# 2020210905-jiajunliANALOG.net
KiCad netlist of a schematic drawn in Altium Designer
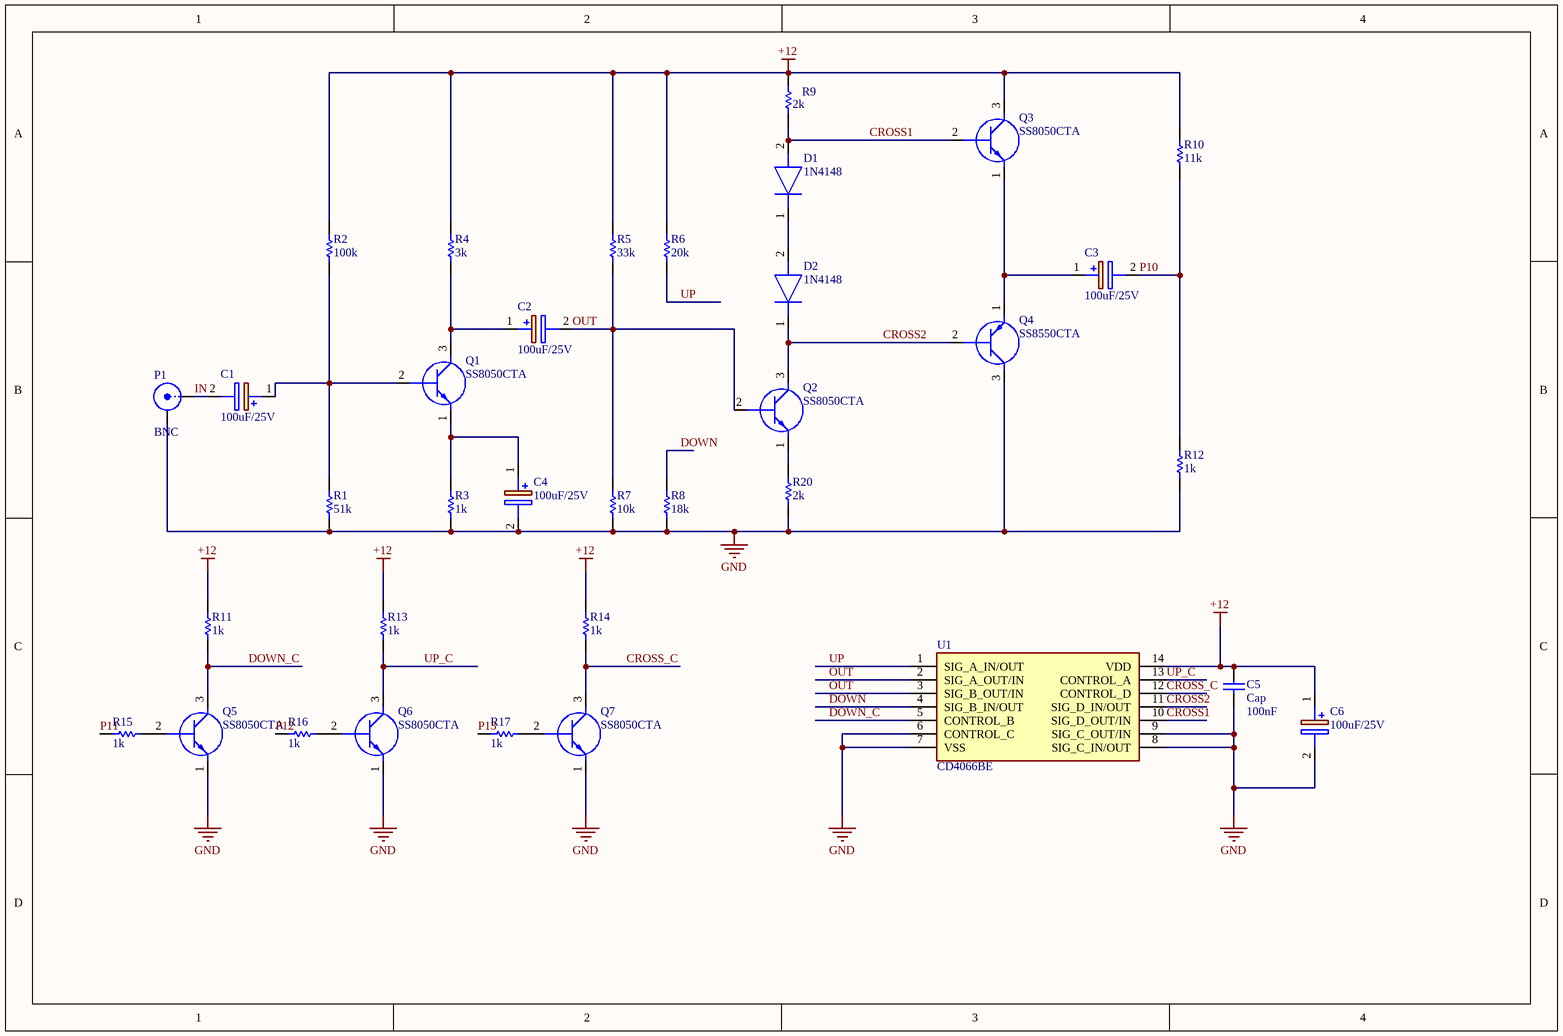
[diagram p0: 2020210905-jiajunliANALOG.SchDoc]

(export (version "E")
  (design (tool "Eeschema 10.0.6"))
  (components
    (comp (ref "C1")
      (value "100uF/25V")
      (footprint "CAPPRD350W65D800H1250")
      (description "Capacitor Polarised")
      (fields
        (field (name "MANUFACTURER_PART_NUMBER") "ECA-1EEN101")
        (field (name "MOUSER PART NUMBER") "667-ECA-1EEN101")
      )
      (libsource (lib "") (part "ECA-1EEN101_1"))
    )
    (comp (ref "C2")
      (value "100uF/25V")
      (footprint "CAPPRD350W65D800H1250")
      (description "Capacitor Polarised")
      (fields
        (field (name "MANUFACTURER_PART_NUMBER") "ECA-1EEN101")
        (field (name "MOUSER PART NUMBER") "667-ECA-1EEN101")
      )
      (libsource (lib "THD-LIB") (part "ECA-1EEN101"))
    )
    (comp (ref "C3")
      (value "100uF/25V")
      (footprint "CAPPRD350W65D800H1250")
      (description "Capacitor Polarised")
      (fields
        (field (name "MANUFACTURER_PART_NUMBER") "ECA-1EEN101")
        (field (name "MOUSER PART NUMBER") "667-ECA-1EEN101")
      )
      (libsource (lib "THD-LIB") (part "ECA-1EEN101"))
    )
    (comp (ref "C4")
      (value "100uF/25V")
      (footprint "CAPPRD350W65D800H1250")
      (description "Capacitor Polarised")
      (fields
        (field (name "MANUFACTURER_PART_NUMBER") "ECA-1EEN101")
        (field (name "MOUSER PART NUMBER") "667-ECA-1EEN101")
      )
      (libsource (lib "") (part "ECA-1EEN101_2"))
    )
    (comp (ref "C5")
      (value "Cap")
      (footprint "RAD-0.2-cap")
      (description "Capacitor")
      (fields (field (name "ALTIUM_VALUE") "100nF") (field (name "PUBLISHER") "Altium Limited"))
      (libsource (lib "THD-LIB") (part "Cap"))
    )
    (comp (ref "C6")
      (value "100uF/25V")
      (footprint "CAPPRD350W65D800H1250")
      (description "Capacitor Polarised")
      (fields
        (field (name "MANUFACTURER_PART_NUMBER") "ECA-1EEN101")
        (field (name "MOUSER PART NUMBER") "667-ECA-1EEN101")
      )
      (libsource (lib "") (part "ECA-1EEN101_2"))
    )
    (comp (ref "D1")
      (value "1N4148")
      (footprint "DIOAD1068W53L380D172")
      (description "Diode")
      (fields (field (name "MOUSER PART NUMBER") "512-1N4148"))
      (libsource (lib "THD-LIB") (part "1N4148"))
    )
    (comp (ref "D2")
      (value "1N4148")
      (footprint "DIOAD1068W53L380D172")
      (description "Diode")
      (fields (field (name "MOUSER PART NUMBER") "512-1N4148"))
      (libsource (lib "THD-LIB") (part "1N4148"))
    )
    (comp (ref "P1")
      (value "BNC")
      (footprint "BNC_RA-CON")
      (description "BNC Elbow Connector")
      (fields (field (name "PUBLISHER") "Altium Limited"))
      (libsource (lib "THD-LIB") (part "BNC"))
    )
    (comp (ref "Q1")
      (value "SS8050CTA")
      (footprint "TO-92-3")
      (description "Transistor BJT NPN")
      (fields (field (name "MOUSER PART NUMBER") "512-SS8050CTA"))
      (libsource (lib "THD-LIB") (part "SS8050CTA"))
    )
    (comp (ref "Q2")
      (value "SS8050CTA")
      (footprint "TO-92-3")
      (description "Transistor BJT NPN")
      (fields (field (name "MOUSER PART NUMBER") "512-SS8050CTA"))
      (libsource (lib "THD-LIB") (part "SS8050CTA"))
    )
    (comp (ref "Q3")
      (value "SS8050CTA")
      (footprint "TO-92-3")
      (description "Transistor BJT NPN")
      (fields (field (name "MOUSER PART NUMBER") "512-SS8050CTA"))
      (libsource (lib "THD-LIB") (part "SS8050CTA"))
    )
    (comp (ref "Q4")
      (value "SS8550CTA")
      (footprint "TO-92-3")
      (description "Transistor BJT PNP")
      (fields (field (name "MOUSER PART NUMBER") "512-SS8550CTA"))
      (libsource (lib "THD-LIB") (part "SS8550CTA"))
    )
    (comp (ref "Q5")
      (value "SS8050CTA")
      (footprint "TO-92-3")
      (description "Transistor BJT NPN")
      (fields (field (name "MOUSER PART NUMBER") "512-SS8050CTA"))
      (libsource (lib "THD-LIB") (part "SS8050CTA"))
    )
    (comp (ref "Q6")
      (value "SS8050CTA")
      (footprint "TO-92-3")
      (description "Transistor BJT NPN")
      (fields (field (name "MOUSER PART NUMBER") "512-SS8050CTA"))
      (libsource (lib "THD-LIB") (part "SS8050CTA"))
    )
    (comp (ref "Q7")
      (value "SS8050CTA")
      (footprint "TO-92-3")
      (description "Transistor BJT NPN")
      (fields (field (name "MOUSER PART NUMBER") "512-SS8050CTA"))
      (libsource (lib "THD-LIB") (part "SS8050CTA"))
    )
    (comp (ref "R1")
      (value "51k")
      (footprint "RES-AXIAL-0.4")
      (description "Resistor")
      (fields (field (name "PUBLISHER") "Altium Limited"))
      (libsource (lib "THD-LIB") (part "Res1"))
    )
    (comp (ref "R2")
      (value "100k")
      (footprint "RES-AXIAL-0.4")
      (description "Resistor")
      (fields (field (name "PUBLISHER") "Altium Limited"))
      (libsource (lib "THD-LIB") (part "Res1"))
    )
    (comp (ref "R3")
      (value "1k")
      (footprint "RES-AXIAL-0.4")
      (description "Resistor")
      (fields (field (name "PUBLISHER") "Altium Limited"))
      (libsource (lib "THD-LIB") (part "Res1"))
    )
    (comp (ref "R4")
      (value "3k")
      (footprint "RES-AXIAL-0.4")
      (description "Resistor")
      (fields (field (name "PUBLISHER") "Altium Limited"))
      (libsource (lib "THD-LIB") (part "Res1"))
    )
    (comp (ref "R5")
      (value "33k")
      (footprint "RES-AXIAL-0.4")
      (description "Resistor")
      (fields (field (name "PUBLISHER") "Altium Limited"))
      (libsource (lib "THD-LIB") (part "Res1"))
    )
    (comp (ref "R6")
      (value "20k")
      (footprint "RES-AXIAL-0.4")
      (description "Resistor")
      (fields (field (name "PUBLISHER") "Altium Limited"))
      (libsource (lib "THD-LIB") (part "Res1"))
    )
    (comp (ref "R7")
      (value "10k")
      (footprint "RES-AXIAL-0.4")
      (description "Resistor")
      (fields (field (name "PUBLISHER") "Altium Limited"))
      (libsource (lib "THD-LIB") (part "Res1"))
    )
    (comp (ref "R8")
      (value "18k")
      (footprint "RES-AXIAL-0.4")
      (description "Resistor")
      (fields (field (name "PUBLISHER") "Altium Limited"))
      (libsource (lib "THD-LIB") (part "Res1"))
    )
    (comp (ref "R9")
      (value "2k")
      (footprint "RES-AXIAL-0.4")
      (description "Resistor")
      (fields (field (name "PUBLISHER") "Altium Limited"))
      (libsource (lib "THD-LIB") (part "Res1"))
    )
    (comp (ref "R10")
      (value "11k")
      (footprint "RES-AXIAL-0.4")
      (description "Resistor")
      (fields (field (name "PUBLISHER") "Altium Limited"))
      (libsource (lib "THD-LIB") (part "Res1"))
    )
    (comp (ref "R11")
      (value "1k")
      (footprint "RES-AXIAL-0.4")
      (description "Resistor")
      (fields (field (name "PUBLISHER") "Altium Limited"))
      (libsource (lib "THD-LIB") (part "Res1"))
    )
    (comp (ref "R12")
      (value "1k")
      (footprint "RES-AXIAL-0.4")
      (description "Resistor")
      (fields (field (name "PUBLISHER") "Altium Limited"))
      (libsource (lib "THD-LIB") (part "Res1"))
    )
    (comp (ref "R13")
      (value "1k")
      (footprint "RES-AXIAL-0.4")
      (description "Resistor")
      (fields (field (name "PUBLISHER") "Altium Limited"))
      (libsource (lib "THD-LIB") (part "Res1"))
    )
    (comp (ref "R14")
      (value "1k")
      (footprint "RES-AXIAL-0.4")
      (description "Resistor")
      (fields (field (name "PUBLISHER") "Altium Limited"))
      (libsource (lib "THD-LIB") (part "Res1"))
    )
    (comp (ref "R15")
      (value "1k")
      (footprint "RES-AXIAL-0.4")
      (description "Resistor")
      (fields (field (name "PUBLISHER") "Altium Limited"))
      (libsource (lib "THD-LIB") (part "Res1"))
    )
    (comp (ref "R16")
      (value "1k")
      (footprint "RES-AXIAL-0.4")
      (description "Resistor")
      (fields (field (name "PUBLISHER") "Altium Limited"))
      (libsource (lib "THD-LIB") (part "Res1"))
    )
    (comp (ref "R17")
      (value "1k")
      (footprint "RES-AXIAL-0.4")
      (description "Resistor")
      (fields (field (name "PUBLISHER") "Altium Limited"))
      (libsource (lib "THD-LIB") (part "Res1"))
    )
    (comp (ref "R20")
      (value "2k")
      (footprint "RES-AXIAL-0.4")
      (description "Resistor")
      (fields (field (name "PUBLISHER") "Altium Limited"))
      (libsource (lib "THD-LIB") (part "Res1"))
    )
    (comp (ref "U1")
      (value "CD4066BE")
      (footprint "DIP794W53P254L1930H508Q14N")
      (description "Integrated Circuit")
      (fields (field (name "MOUSER PART NUMBER") "595-CD4066BE"))
      (libsource (lib "THD-LIB") (part "CD4066BE"))
    )
  )
  (nets
    (net (code "1") (name "+12") (class "Default")
      (node (ref "C5") (pin "2") (pinfunction "2_2") (pintype "passive"))
      (node (ref "C6") (pin "1") (pinfunction "+_1") (pintype "passive"))
      (node (ref "Q3") (pin "3") (pinfunction "C_3") (pintype "passive"))
      (node (ref "R10") (pin "2") (pinfunction "2_2") (pintype "passive"))
      (node (ref "R11") (pin "2") (pinfunction "2_2") (pintype "passive"))
      (node (ref "R13") (pin "2") (pinfunction "2_2") (pintype "passive"))
      (node (ref "R14") (pin "2") (pinfunction "2_2") (pintype "passive"))
      (node (ref "R2") (pin "2") (pinfunction "2_2") (pintype "passive"))
      (node (ref "R4") (pin "2") (pinfunction "2_2") (pintype "passive"))
      (node (ref "R5") (pin "2") (pinfunction "2_2") (pintype "passive"))
      (node (ref "R6") (pin "2") (pinfunction "2_2") (pintype "passive"))
      (node (ref "R9") (pin "2") (pinfunction "2_2") (pintype "passive"))
      (node (ref "U1") (pin "14") (pinfunction "VDD_14") (pintype "passive"))
    )
    (net (code "2") (name "/CROSS1") (class "Default")
      (node (ref "D1") (pin "2") (pinfunction "A_2") (pintype "passive"))
      (node (ref "Q3") (pin "2") (pinfunction "B_2") (pintype "passive"))
      (node (ref "R9") (pin "1") (pinfunction "1_1") (pintype "passive"))
      (node (ref "U1") (pin "10") (pinfunction "SIG_D_OUT/IN_10") (pintype "passive"))
    )
    (net (code "3") (name "/CROSS2") (class "Default")
      (node (ref "D2") (pin "1") (pinfunction "K_1") (pintype "passive"))
      (node (ref "Q2") (pin "3") (pinfunction "C_3") (pintype "passive"))
      (node (ref "Q4") (pin "2") (pinfunction "B_2") (pintype "passive"))
      (node (ref "U1") (pin "11") (pinfunction "SIG_D_IN/OUT_11") (pintype "passive"))
    )
    (net (code "4") (name "/CROSS_C") (class "Default")
      (node (ref "Q7") (pin "3") (pinfunction "C_3") (pintype "passive"))
      (node (ref "R14") (pin "1") (pinfunction "1_1") (pintype "passive"))
      (node (ref "U1") (pin "12") (pinfunction "CONTROL_D_12") (pintype "passive"))
    )
    (net (code "5") (name "/DOWN") (class "Default")
      (node (ref "R8") (pin "2") (pinfunction "2_2") (pintype "passive"))
      (node (ref "U1") (pin "4") (pinfunction "SIG_B_IN/OUT_4") (pintype "passive"))
    )
    (net (code "6") (name "/DOWN_C") (class "Default")
      (node (ref "Q5") (pin "3") (pinfunction "C_3") (pintype "passive"))
      (node (ref "R11") (pin "1") (pinfunction "1_1") (pintype "passive"))
      (node (ref "U1") (pin "5") (pinfunction "CONTROL_B_5") (pintype "passive"))
    )
    (net (code "7") (name "/IN") (class "Default")
      (node (ref "C1") (pin "2") (pinfunction "-_2") (pintype "passive"))
      (node (ref "P1") (pin "1") (pinfunction "X_1") (pintype "passive"))
    )
    (net (code "8") (name "/OUT") (class "Default")
      (node (ref "C2") (pin "2") (pinfunction "-_2") (pintype "passive"))
      (node (ref "Q2") (pin "2") (pinfunction "B_2") (pintype "passive"))
      (node (ref "R5") (pin "1") (pinfunction "1_1") (pintype "passive"))
      (node (ref "R7") (pin "2") (pinfunction "2_2") (pintype "passive"))
      (node (ref "U1") (pin "2") (pinfunction "SIG_A_OUT/IN_2") (pintype "passive"))
      (node (ref "U1") (pin "3") (pinfunction "SIG_B_OUT/IN_3") (pintype "passive"))
    )
    (net (code "9") (name "/P10") (class "Default")
      (node (ref "C3") (pin "2") (pinfunction "-_2") (pintype "passive"))
      (node (ref "R10") (pin "1") (pinfunction "1_1") (pintype "passive"))
      (node (ref "R12") (pin "2") (pinfunction "2_2") (pintype "passive"))
    )
    (net (code "10") (name "/P11") (class "Default")
      (node (ref "R15") (pin "2") (pinfunction "2_2") (pintype "passive"))
    )
    (net (code "11") (name "/P12") (class "Default")
      (node (ref "R16") (pin "2") (pinfunction "2_2") (pintype "passive"))
    )
    (net (code "12") (name "/P13") (class "Default")
      (node (ref "R17") (pin "2") (pinfunction "2_2") (pintype "passive"))
    )
    (net (code "13") (name "/UP") (class "Default")
      (node (ref "R6") (pin "1") (pinfunction "1_1") (pintype "passive"))
      (node (ref "U1") (pin "1") (pinfunction "SIG_A_IN/OUT_1") (pintype "passive"))
    )
    (net (code "14") (name "/UP_C") (class "Default")
      (node (ref "Q6") (pin "3") (pinfunction "C_3") (pintype "passive"))
      (node (ref "R13") (pin "1") (pinfunction "1_1") (pintype "passive"))
      (node (ref "U1") (pin "13") (pinfunction "CONTROL_A_13") (pintype "passive"))
    )
    (net (code "15") (name "GND") (class "Default")
      (node (ref "C4") (pin "2") (pinfunction "-_2") (pintype "passive"))
      (node (ref "C5") (pin "1") (pinfunction "1_1") (pintype "passive"))
      (node (ref "C6") (pin "2") (pinfunction "-_2") (pintype "passive"))
      (node (ref "P1") (pin "2") (pinfunction "Y_2") (pintype "passive"))
      (node (ref "Q4") (pin "3") (pinfunction "C_3") (pintype "passive"))
      (node (ref "Q5") (pin "1") (pinfunction "E_1") (pintype "passive"))
      (node (ref "Q6") (pin "1") (pinfunction "E_1") (pintype "passive"))
      (node (ref "Q7") (pin "1") (pinfunction "E_1") (pintype "passive"))
      (node (ref "R1") (pin "1") (pinfunction "1_1") (pintype "passive"))
      (node (ref "R12") (pin "1") (pinfunction "1_1") (pintype "passive"))
      (node (ref "R20") (pin "1") (pinfunction "1_1") (pintype "passive"))
      (node (ref "R3") (pin "1") (pinfunction "1_1") (pintype "passive"))
      (node (ref "R7") (pin "1") (pinfunction "1_1") (pintype "passive"))
      (node (ref "R8") (pin "1") (pinfunction "1_1") (pintype "passive"))
      (node (ref "U1") (pin "6") (pinfunction "CONTROL_C_6") (pintype "passive"))
      (node (ref "U1") (pin "7") (pinfunction "VSS_7") (pintype "passive"))
      (node (ref "U1") (pin "8") (pinfunction "SIG_C_IN/OUT_8") (pintype "passive"))
      (node (ref "U1") (pin "9") (pinfunction "SIG_C_OUT/IN_9") (pintype "passive"))
    )
    (net (code "16") (name "Net-(C1-+)") (class "Default")
      (node (ref "C1") (pin "1") (pinfunction "+_1") (pintype "passive"))
      (node (ref "Q1") (pin "2") (pinfunction "B_2") (pintype "passive"))
      (node (ref "R1") (pin "2") (pinfunction "2_2") (pintype "passive"))
      (node (ref "R2") (pin "1") (pinfunction "1_1") (pintype "passive"))
    )
    (net (code "17") (name "Net-(C2-+)") (class "Default")
      (node (ref "C2") (pin "1") (pinfunction "+_1") (pintype "passive"))
      (node (ref "Q1") (pin "3") (pinfunction "C_3") (pintype "passive"))
      (node (ref "R4") (pin "1") (pinfunction "1_1") (pintype "passive"))
    )
    (net (code "18") (name "Net-(C3-+)") (class "Default")
      (node (ref "C3") (pin "1") (pinfunction "+_1") (pintype "passive"))
      (node (ref "Q3") (pin "1") (pinfunction "E_1") (pintype "passive"))
      (node (ref "Q4") (pin "1") (pinfunction "E_1") (pintype "passive"))
    )
    (net (code "19") (name "Net-(C4-+)") (class "Default")
      (node (ref "C4") (pin "1") (pinfunction "+_1") (pintype "passive"))
      (node (ref "Q1") (pin "1") (pinfunction "E_1") (pintype "passive"))
      (node (ref "R3") (pin "2") (pinfunction "2_2") (pintype "passive"))
    )
    (net (code "20") (name "Net-(D1-K)") (class "Default")
      (node (ref "D1") (pin "1") (pinfunction "K_1") (pintype "passive"))
      (node (ref "D2") (pin "2") (pinfunction "A_2") (pintype "passive"))
    )
    (net (code "21") (name "Net-(Q2-E)") (class "Default")
      (node (ref "Q2") (pin "1") (pinfunction "E_1") (pintype "passive"))
      (node (ref "R20") (pin "2") (pinfunction "2_2") (pintype "passive"))
    )
    (net (code "22") (name "Net-(Q5-B)") (class "Default")
      (node (ref "Q5") (pin "2") (pinfunction "B_2") (pintype "passive"))
      (node (ref "R15") (pin "1") (pinfunction "1_1") (pintype "passive"))
    )
    (net (code "23") (name "Net-(Q6-B)") (class "Default")
      (node (ref "Q6") (pin "2") (pinfunction "B_2") (pintype "passive"))
      (node (ref "R16") (pin "1") (pinfunction "1_1") (pintype "passive"))
    )
    (net (code "24") (name "Net-(Q7-B)") (class "Default")
      (node (ref "Q7") (pin "2") (pinfunction "B_2") (pintype "passive"))
      (node (ref "R17") (pin "1") (pinfunction "1_1") (pintype "passive"))
    )
  )
)
